# temp_board2_-_itr2_V2.net
KiCad netlist of a schematic drawn in EAGLE
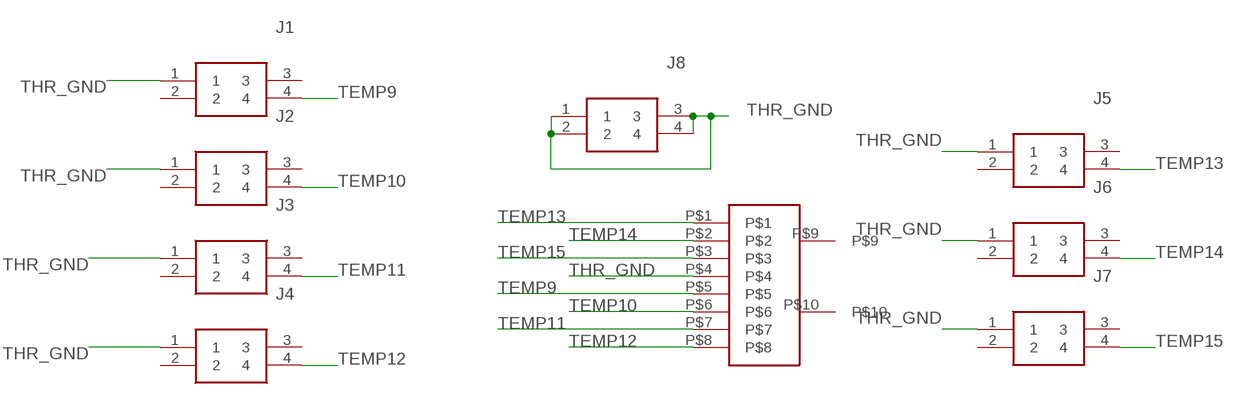
[diagram p0: schematic, sheet 1]

(export (version "E")
  (design (tool "Eeschema 10.0.6"))
  (components
    (comp (ref "J1")
      (value "43045-0415")
      (footprint "eagle-import:43045-04YY_15,16,17")
      (fields (field (name "MOUSER_PART_NUMBER") "538-43045-0415"))
      (libsource (lib "eagle-import") (part "43045-0415"))
    )
    (comp (ref "J2")
      (value "43045-0415")
      (footprint "eagle-import:43045-04YY_15,16,17")
      (fields (field (name "MOUSER_PART_NUMBER") "538-43045-0415"))
      (libsource (lib "eagle-import") (part "43045-0415"))
    )
    (comp (ref "J3")
      (value "43045-0415")
      (footprint "eagle-import:43045-04YY_15,16,17")
      (fields (field (name "MOUSER_PART_NUMBER") "538-43045-0415"))
      (libsource (lib "eagle-import") (part "43045-0415"))
    )
    (comp (ref "J4")
      (value "43045-0415")
      (footprint "eagle-import:43045-04YY_15,16,17")
      (fields (field (name "MOUSER_PART_NUMBER") "538-43045-0415"))
      (libsource (lib "eagle-import") (part "43045-0415"))
    )
    (comp (ref "J5")
      (value "43045-0415")
      (footprint "eagle-import:43045-04YY_15,16,17")
      (fields (field (name "MOUSER_PART_NUMBER") "538-43045-0415"))
      (libsource (lib "eagle-import") (part "43045-0415"))
    )
    (comp (ref "J6")
      (value "43045-0415")
      (footprint "eagle-import:43045-04YY_15,16,17")
      (fields (field (name "MOUSER_PART_NUMBER") "538-43045-0415"))
      (libsource (lib "eagle-import") (part "43045-0415"))
    )
    (comp (ref "J7")
      (value "43045-0415")
      (footprint "eagle-import:43045-04YY_15,16,17")
      (fields (field (name "MOUSER_PART_NUMBER") "538-43045-0415"))
      (libsource (lib "eagle-import") (part "43045-0415"))
    )
    (comp (ref "J8")
      (value "43045-0415")
      (footprint "eagle-import:43045-04YY_15,16,17")
      (fields (field (name "MOUSER_PART_NUMBER") "538-43045-0415"))
      (libsource (lib "eagle-import") (part "43045-0415"))
    )
    (comp (ref "U$36")
      (value "VERTICALBMS8")
      (footprint "eagle-import:VERTICALBMS8")
      (libsource (lib "eagle-import") (part "VERTICALBMS8"))
    )
  )
  (nets
    (net (code "1") (name "/TEMP9") (class "Default")
      (node (ref "J1") (pin "4") (pinfunction "4_4") (pintype "bidirectional"))
      (node (ref "U$36") (pin "P$5") (pinfunction "P$5_P$5") (pintype "bidirectional"))
    )
    (net (code "2") (name "/TEMP10") (class "Default")
      (node (ref "J2") (pin "4") (pinfunction "4_4") (pintype "bidirectional"))
      (node (ref "U$36") (pin "P$6") (pinfunction "P$6_P$6") (pintype "bidirectional"))
    )
    (net (code "3") (name "/TEMP11") (class "Default")
      (node (ref "J3") (pin "4") (pinfunction "4_4") (pintype "bidirectional"))
      (node (ref "U$36") (pin "P$7") (pinfunction "P$7_P$7") (pintype "bidirectional"))
    )
    (net (code "4") (name "/TEMP12") (class "Default")
      (node (ref "J4") (pin "4") (pinfunction "4_4") (pintype "bidirectional"))
      (node (ref "U$36") (pin "P$8") (pinfunction "P$8_P$8") (pintype "bidirectional"))
    )
    (net (code "5") (name "/TEMP13") (class "Default")
      (node (ref "J5") (pin "4") (pinfunction "4_4") (pintype "bidirectional"))
      (node (ref "U$36") (pin "P$1") (pinfunction "P$1_P$1") (pintype "bidirectional"))
    )
    (net (code "6") (name "/TEMP14") (class "Default")
      (node (ref "J6") (pin "4") (pinfunction "4_4") (pintype "bidirectional"))
      (node (ref "U$36") (pin "P$2") (pinfunction "P$2_P$2") (pintype "bidirectional"))
    )
    (net (code "7") (name "/TEMP15") (class "Default")
      (node (ref "J7") (pin "4") (pinfunction "4_4") (pintype "bidirectional"))
      (node (ref "U$36") (pin "P$3") (pinfunction "P$3_P$3") (pintype "bidirectional"))
    )
    (net (code "8") (name "/THR_GND") (class "Default")
      (node (ref "J1") (pin "1") (pinfunction "1_1") (pintype "bidirectional"))
      (node (ref "J2") (pin "1") (pinfunction "1_1") (pintype "bidirectional"))
      (node (ref "J3") (pin "1") (pinfunction "1_1") (pintype "bidirectional"))
      (node (ref "J4") (pin "1") (pinfunction "1_1") (pintype "bidirectional"))
      (node (ref "J5") (pin "1") (pinfunction "1_1") (pintype "bidirectional"))
      (node (ref "J6") (pin "1") (pinfunction "1_1") (pintype "bidirectional"))
      (node (ref "J7") (pin "1") (pinfunction "1_1") (pintype "bidirectional"))
      (node (ref "J8") (pin "1") (pinfunction "1_1") (pintype "bidirectional"))
      (node (ref "J8") (pin "2") (pinfunction "2_2") (pintype "bidirectional"))
      (node (ref "J8") (pin "3") (pinfunction "3_3") (pintype "bidirectional"))
      (node (ref "J8") (pin "4") (pinfunction "4_4") (pintype "bidirectional"))
      (node (ref "U$36") (pin "P$4") (pinfunction "P$4_P$4") (pintype "bidirectional"))
    )
    (net (code "9") (name "unconnected-(J1-Pad2)") (class "Default")
      (node (ref "J1") (pin "2") (pinfunction "2_2") (pintype "bidirectional"))
    )
    (net (code "10") (name "unconnected-(J1-Pad3)") (class "Default")
      (node (ref "J1") (pin "3") (pinfunction "3_3") (pintype "bidirectional"))
    )
    (net (code "11") (name "unconnected-(J2-Pad2)") (class "Default")
      (node (ref "J2") (pin "2") (pinfunction "2_2") (pintype "bidirectional"))
    )
    (net (code "12") (name "unconnected-(J2-Pad3)") (class "Default")
      (node (ref "J2") (pin "3") (pinfunction "3_3") (pintype "bidirectional"))
    )
    (net (code "13") (name "unconnected-(J3-Pad2)") (class "Default")
      (node (ref "J3") (pin "2") (pinfunction "2_2") (pintype "bidirectional"))
    )
    (net (code "14") (name "unconnected-(J3-Pad3)") (class "Default")
      (node (ref "J3") (pin "3") (pinfunction "3_3") (pintype "bidirectional"))
    )
    (net (code "15") (name "unconnected-(J4-Pad2)") (class "Default")
      (node (ref "J4") (pin "2") (pinfunction "2_2") (pintype "bidirectional"))
    )
    (net (code "16") (name "unconnected-(J4-Pad3)") (class "Default")
      (node (ref "J4") (pin "3") (pinfunction "3_3") (pintype "bidirectional"))
    )
    (net (code "17") (name "unconnected-(J5-Pad2)") (class "Default")
      (node (ref "J5") (pin "2") (pinfunction "2_2") (pintype "bidirectional"))
    )
    (net (code "18") (name "unconnected-(J5-Pad3)") (class "Default")
      (node (ref "J5") (pin "3") (pinfunction "3_3") (pintype "bidirectional"))
    )
    (net (code "19") (name "unconnected-(J6-Pad2)") (class "Default")
      (node (ref "J6") (pin "2") (pinfunction "2_2") (pintype "bidirectional"))
    )
    (net (code "20") (name "unconnected-(J6-Pad3)") (class "Default")
      (node (ref "J6") (pin "3") (pinfunction "3_3") (pintype "bidirectional"))
    )
    (net (code "21") (name "unconnected-(J7-Pad2)") (class "Default")
      (node (ref "J7") (pin "2") (pinfunction "2_2") (pintype "bidirectional"))
    )
    (net (code "22") (name "unconnected-(J7-Pad3)") (class "Default")
      (node (ref "J7") (pin "3") (pinfunction "3_3") (pintype "bidirectional"))
    )
    (net (code "23") (name "unconnected-(U$36-PadP$9)") (class "Default")
      (node (ref "U$36") (pin "P$9") (pinfunction "P$9_P$9") (pintype "bidirectional"))
    )
    (net (code "24") (name "unconnected-(U$36-PadP$10)") (class "Default")
      (node (ref "U$36") (pin "P$10") (pinfunction "P$10_P$10") (pintype "bidirectional"))
    )
  )
)
